# 1-Schematic_New_Project2.net
KiCad netlist of a schematic drawn in EasyEDA
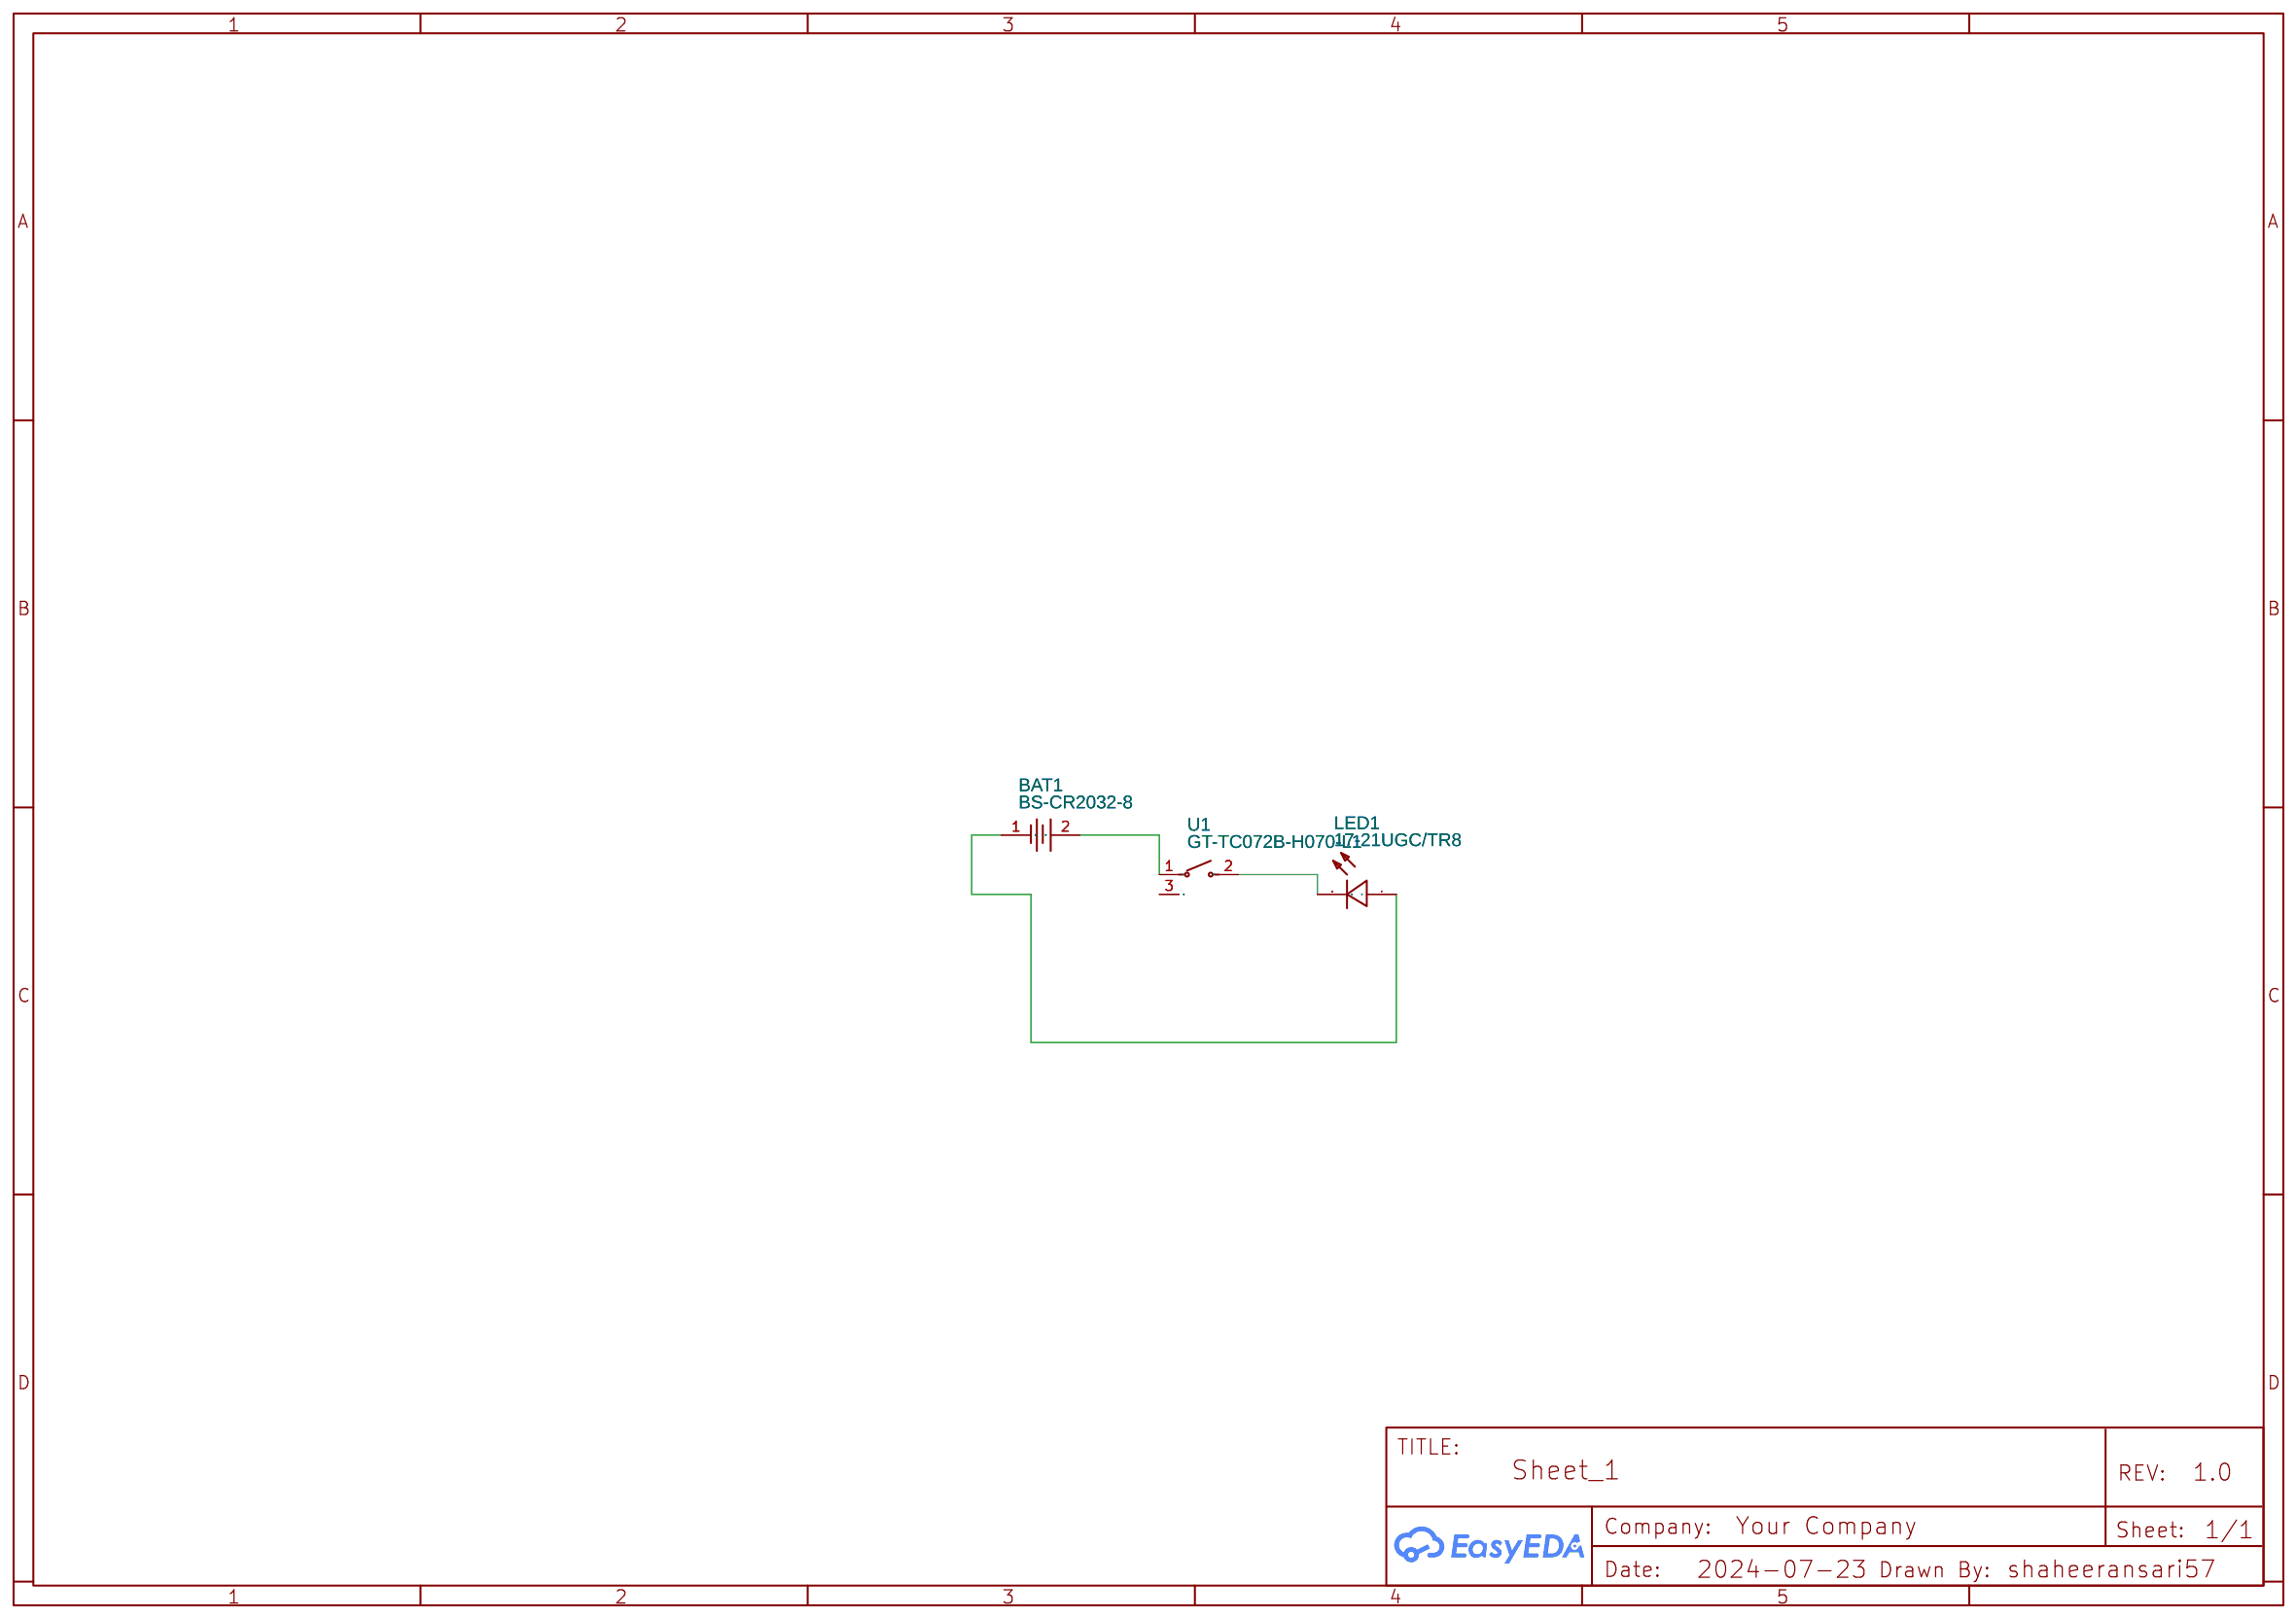
[diagram p0: schematic sheet]

(export (version "E")
  (design (tool "Eeschema 10.0.6"))
  (components
    (comp (ref "BAT1")
      (value "BS-CR2032-8")
      (fields (field (name "Manufacturer") "LX(连欣科技)"))
      (libsource (lib "") (part "BS-CR2032-8"))
    )
    (comp (ref "LED1")
      (value "17-21UGC/TR8")
      (fields (field (name "Manufacturer") "EVERLIGHT(亿光)"))
      (libsource (lib "") (part "17-21UGC/TR8"))
    )
    (comp (ref "U1")
      (value "GT-TC072B-H070-L1")
      (fields (field (name "Manufacturer") "G-Switch(品赞)"))
      (libsource (lib "") (part "GT-TC072B-H070-L1"))
    )
  )
  (nets
    (net (code "1") (name "Net-(BAT1-Pad2)") (class "Default")
      (node (ref "BAT1") (pin "2") (pinfunction "2_2") (pintype "input"))
      (node (ref "U1") (pin "1") (pinfunction "1_1") (pintype "unspecified"))
    )
    (net (code "2") (name "Net-(LED1-A)") (class "Default")
      (node (ref "BAT1") (pin "1") (pinfunction "1_1") (pintype "input"))
      (node (ref "LED1") (pin "1") (pinfunction "A_1") (pintype "unspecified"))
    )
    (net (code "3") (name "Net-(LED1-K)") (class "Default")
      (node (ref "LED1") (pin "2") (pinfunction "K_2") (pintype "unspecified"))
      (node (ref "U1") (pin "2") (pinfunction "2_2") (pintype "unspecified"))
    )
    (net (code "4") (name "unconnected-(U1-Pad3)") (class "Default")
      (node (ref "U1") (pin "3") (pinfunction "3_3") (pintype "unspecified"))
    )
  )
)
